# Papra_v0_10.net
KiCad netlist of a schematic drawn in EAGLE
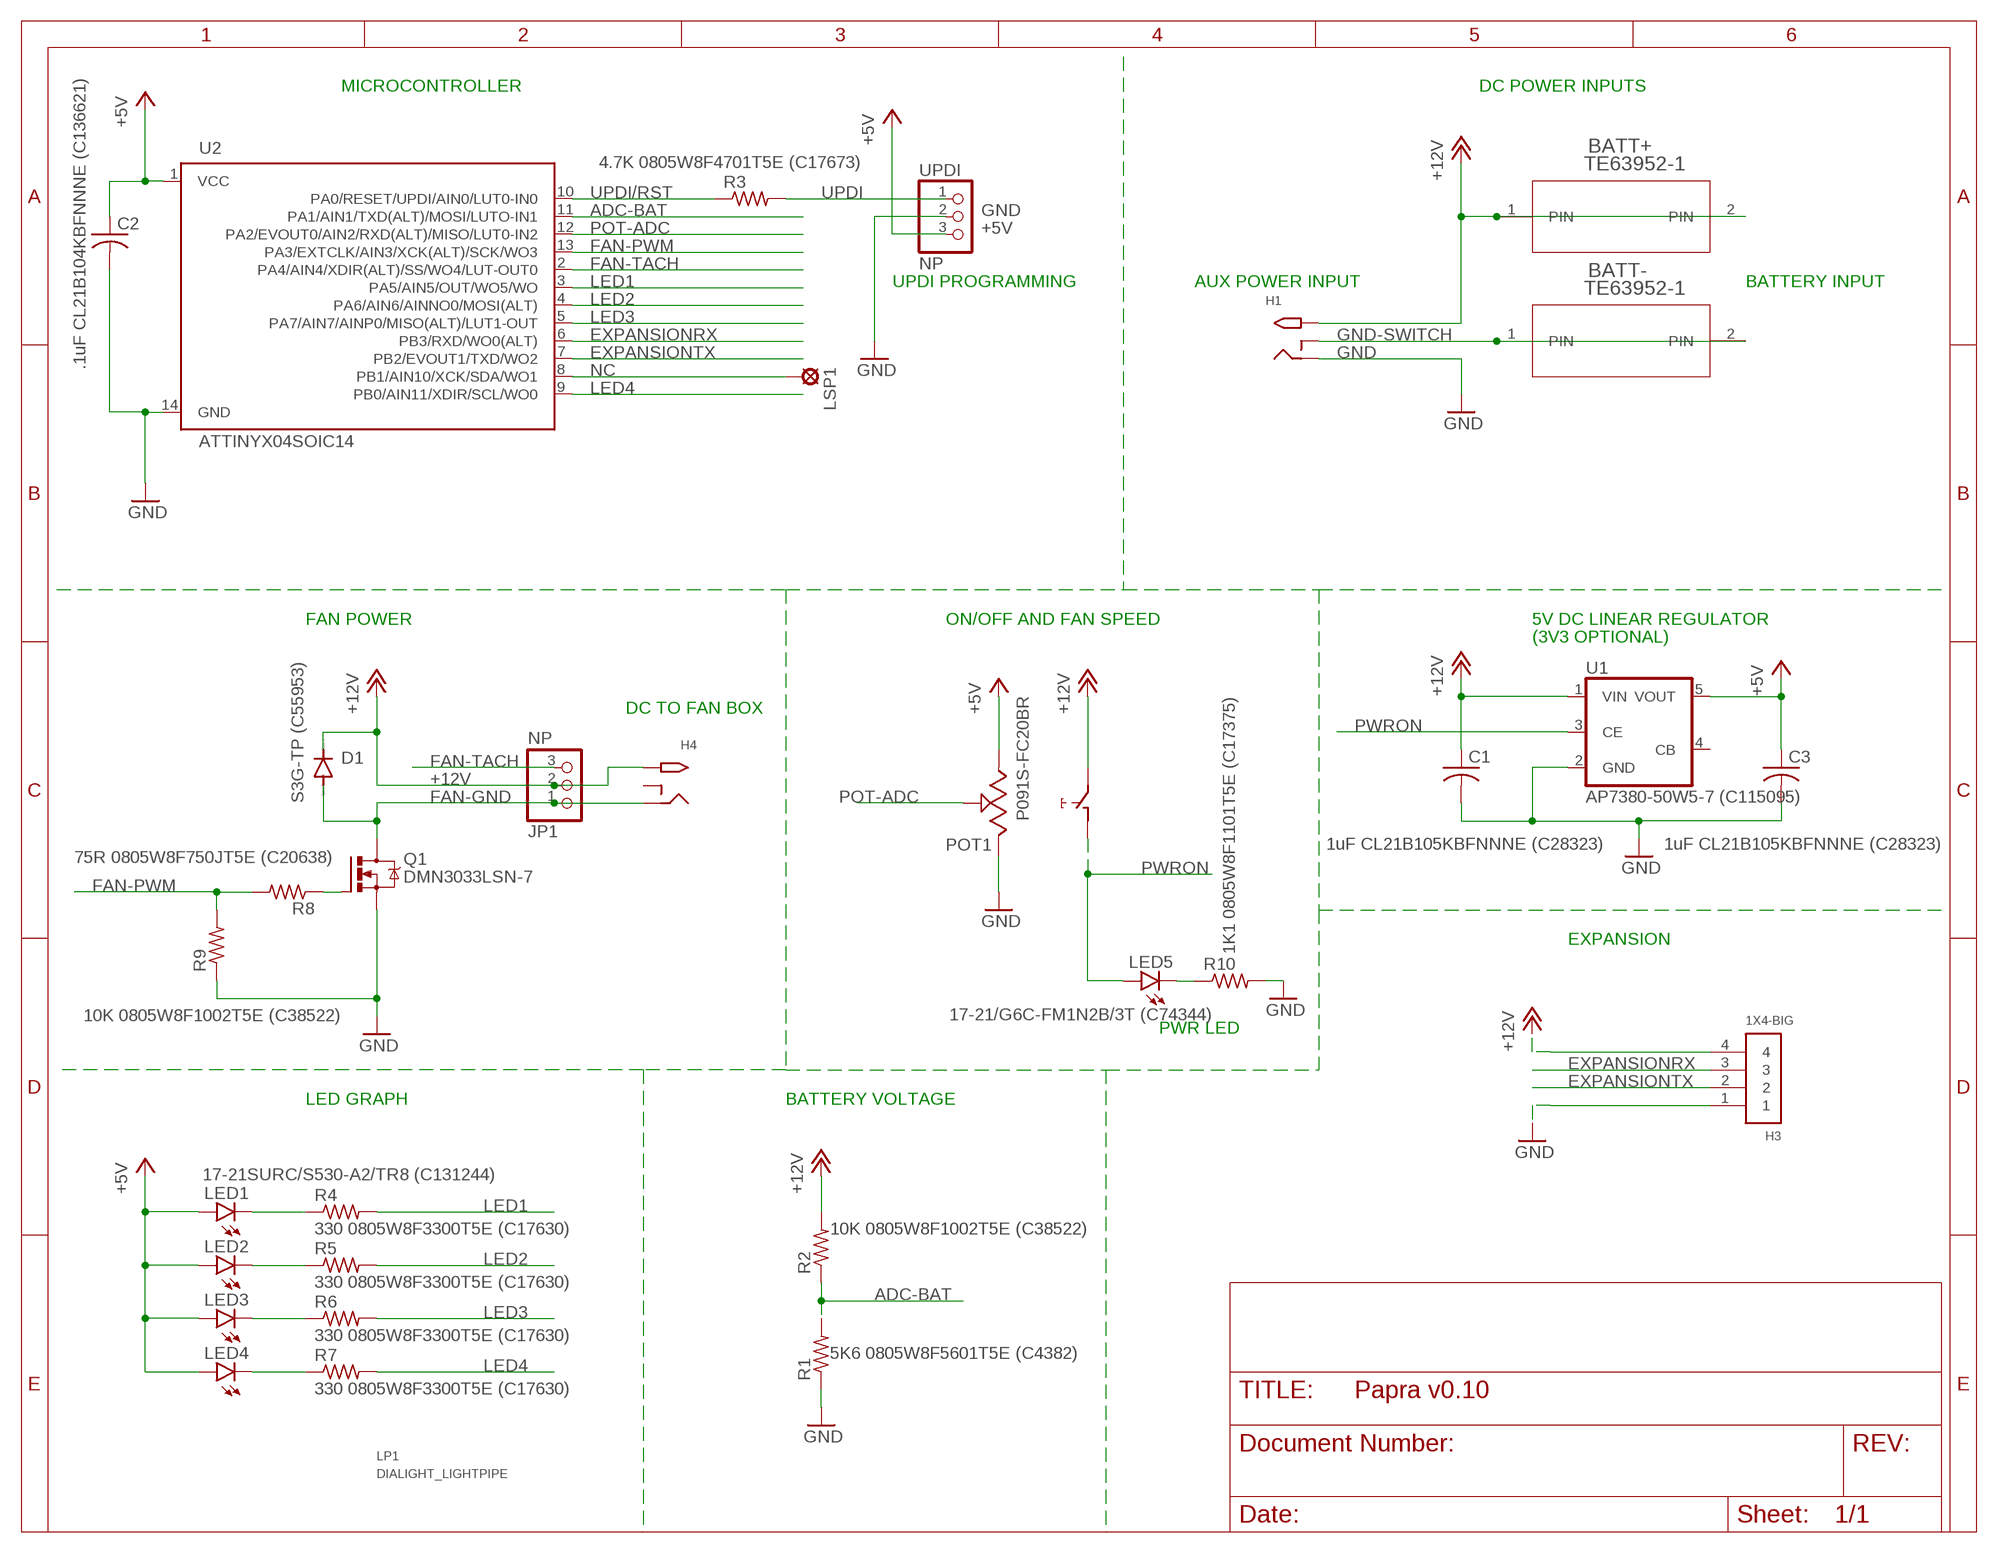
[diagram p0: schematic, sheet 1]

(export (version "E")
  (design (tool "Eeschema 10.0.6"))
  (components
    (comp (ref "BATT+")
      (value "TE63952-1")
      (footprint "eagle-import:TE63952-1")
      (libsource (lib "eagle-import") (part "TE63952-1"))
    )
    (comp (ref "BATT-")
      (value "TE63952-1")
      (footprint "eagle-import:TE63952-1")
      (libsource (lib "eagle-import") (part "TE63952-1"))
    )
    (comp (ref "C1")
      (value "1uF CL21B105KBFNNNE (C28323)")
      (footprint "eagle-import:C0805")
      (libsource (lib "eagle-import") (part "C-USC0805"))
    )
    (comp (ref "C2")
      (value ".1uF CL21B104KBFNNNE (C136621)")
      (footprint "eagle-import:C0805")
      (libsource (lib "eagle-import") (part "C-USC0805"))
    )
    (comp (ref "C3")
      (value "1uF CL21B105KBFNNNE (C28323)")
      (footprint "eagle-import:C0805")
      (libsource (lib "eagle-import") (part "C-USC0805"))
    )
    (comp (ref "D1")
      (value "S3G-TP (C55953)")
      (footprint "eagle-import:SMC")
      (libsource (lib "eagle-import") (part "DIODE-SMC"))
    )
    (comp (ref "H1")
      (value "M-CUI-PJ-066A")
      (footprint "eagle-import:DCJACK-PJ-066A")
      (libsource (lib "eagle-import") (part "PJ-066A"))
    )
    (comp (ref "H3")
      (value "1X4-BIG")
      (footprint "eagle-import:1X04-BIG")
      (libsource (lib "eagle-import") (part "1X4-BIG"))
    )
    (comp (ref "H4")
      (value "M-CUI-PJ-066A")
      (footprint "eagle-import:DCJACK-PJ-066A")
      (libsource (lib "eagle-import") (part "PJ-066A"))
    )
    (comp (ref "JP1")
      (value "NP")
      (footprint "eagle-import:1X03")
      (libsource (lib "eagle-import") (part "PINHD-1X3"))
    )
    (comp (ref "LED1")
      (value "17-21SURC/S530-A2/TR8 (C131244)")
      (footprint "eagle-import:CHIPLED_0805")
      (libsource (lib "eagle-import") (part "LEDCHIPLED_0805"))
    )
    (comp (ref "LED2")
      (value "17-21SURC/S530-A2/TR8 (C131244)")
      (footprint "eagle-import:CHIPLED_0805")
      (libsource (lib "eagle-import") (part "LEDCHIPLED_0805"))
    )
    (comp (ref "LED3")
      (value "17-21SURC/S530-A2/TR8 (C131244)")
      (footprint "eagle-import:CHIPLED_0805")
      (libsource (lib "eagle-import") (part "LEDCHIPLED_0805"))
    )
    (comp (ref "LED4")
      (value "17-21SURC/S530-A2/TR8 (C131244)")
      (footprint "eagle-import:CHIPLED_0805")
      (libsource (lib "eagle-import") (part "LEDCHIPLED_0805"))
    )
    (comp (ref "LED5")
      (value "17-21/G6C-FM1N2B/3T (C74344)")
      (footprint "eagle-import:CHIPLED_0805")
      (libsource (lib "eagle-import") (part "LEDCHIPLED_0805"))
    )
    (comp (ref "LP1")
      (value "DIALIGHT_LIGHTPIPE")
      (footprint "eagle-import:DIALIGHT_5151020F__LEDS")
      (libsource (lib "eagle-import") (part "DIALIGHT_LIGHTPIPE"))
    )
    (comp (ref "LSP1")
      (value "SE13")
      (footprint "eagle-import:SE13")
      (libsource (lib "eagle-import") (part "SE13"))
    )
    (comp (ref "POT1")
      (value "P091S-FC20BR")
      (footprint "eagle-import:P091S-FC20BR")
      (libsource (lib "eagle-import") (part "P091S-FC20BR"))
    )
    (comp (ref "Q1")
      (value "DMN3033LSN-7")
      (footprint "eagle-import:SOT23")
      (libsource (lib "eagle-import") (part "NMOSFETSOT23"))
    )
    (comp (ref "R1")
      (value "5K6 0805W8F5601T5E (C4382)")
      (footprint "eagle-import:R0805")
      (libsource (lib "eagle-import") (part "R-US_R0805"))
    )
    (comp (ref "R2")
      (value "10K 0805W8F1002T5E (C38522)")
      (footprint "eagle-import:R0805")
      (libsource (lib "eagle-import") (part "R-US_R0805"))
    )
    (comp (ref "R3")
      (value "4.7K 0805W8F4701T5E (C17673)")
      (footprint "eagle-import:R0805")
      (libsource (lib "eagle-import") (part "R-US_R0805"))
    )
    (comp (ref "R4")
      (value "330 0805W8F3300T5E (C17630)")
      (footprint "eagle-import:R0805")
      (libsource (lib "eagle-import") (part "R-US_R0805"))
    )
    (comp (ref "R5")
      (value "330 0805W8F3300T5E (C17630)")
      (footprint "eagle-import:R0805")
      (libsource (lib "eagle-import") (part "R-US_R0805"))
    )
    (comp (ref "R6")
      (value "330 0805W8F3300T5E (C17630)")
      (footprint "eagle-import:R0805")
      (libsource (lib "eagle-import") (part "R-US_R0805"))
    )
    (comp (ref "R7")
      (value "330 0805W8F3300T5E (C17630)")
      (footprint "eagle-import:R0805")
      (libsource (lib "eagle-import") (part "R-US_R0805"))
    )
    (comp (ref "R8")
      (value "75R 0805W8F750JT5E (C20638)")
      (footprint "eagle-import:R0805")
      (libsource (lib "eagle-import") (part "R-US_R0805"))
    )
    (comp (ref "R9")
      (value "10K 0805W8F1002T5E (C38522)")
      (footprint "eagle-import:R0805")
      (libsource (lib "eagle-import") (part "R-US_R0805"))
    )
    (comp (ref "R10")
      (value "1K1 0805W8F1101T5E (C17375)")
      (footprint "eagle-import:R0805")
      (libsource (lib "eagle-import") (part "R-US_R0805"))
    )
    (comp (ref "U1")
      (value "AP7380-50W5-7 (C115095)")
      (footprint "eagle-import:SOT25")
      (libsource (lib "eagle-import") (part "TS520533"))
    )
    (comp (ref "U2")
      (value "ATTINYX04SOIC14")
      (footprint "eagle-import:SOIC127P600X144-14")
      (libsource (lib "eagle-import") (part "ATTINYX04SOIC14"))
    )
    (comp (ref "UPDI")
      (value "NP")
      (footprint "eagle-import:1X03")
      (libsource (lib "eagle-import") (part "PINHD-1X3"))
    )
  )
  (nets
    (net (code "1") (name "+5V") (class "Default")
      (node (ref "C2") (pin "1") (pinfunction "1_1") (pintype "passive"))
      (node (ref "C3") (pin "1") (pinfunction "1_1") (pintype "passive"))
      (node (ref "LED1") (pin "A") (pinfunction "A_A") (pintype "passive"))
      (node (ref "LED2") (pin "A") (pinfunction "A_A") (pintype "passive"))
      (node (ref "LED3") (pin "A") (pinfunction "A_A") (pintype "passive"))
      (node (ref "LED4") (pin "A") (pinfunction "A_A") (pintype "passive"))
      (node (ref "POT1") (pin "1") (pinfunction "1_1") (pintype "passive"))
      (node (ref "U1") (pin "5") (pinfunction "VOUT_5") (pintype "passive"))
      (node (ref "U2") (pin "1") (pinfunction "VCC_1") (pintype "power_in"))
      (node (ref "UPDI") (pin "3") (pinfunction "3_3") (pintype "passive"))
    )
    (net (code "2") (name "+12V") (class "Default")
      (node (ref "BATT+") (pin "1") (pinfunction "PIN_1") (pintype "passive"))
      (node (ref "BATT+") (pin "2") (pinfunction "PIN_2") (pintype "passive"))
      (node (ref "C1") (pin "1") (pinfunction "1_1") (pintype "passive"))
      (node (ref "D1") (pin "C") (pinfunction "C_C") (pintype "passive"))
      (node (ref "H1") (pin "PWR") (pinfunction "TIP_PWR") (pintype "bidirectional"))
      (node (ref "H3") (pin "4") (pinfunction "4_4") (pintype "bidirectional"))
      (node (ref "H4") (pin "PWR") (pinfunction "TIP_PWR") (pintype "bidirectional"))
      (node (ref "JP1") (pin "2") (pinfunction "2_2") (pintype "passive"))
      (node (ref "POT1") (pin "NO") (pinfunction "5_NO") (pintype "passive"))
      (node (ref "R2") (pin "2") (pinfunction "2_2") (pintype "passive"))
      (node (ref "U1") (pin "1") (pinfunction "VIN_1") (pintype "input"))
    )
    (net (code "3") (name "/ADC-BAT") (class "Default")
      (node (ref "R1") (pin "2") (pinfunction "2_2") (pintype "passive"))
      (node (ref "R2") (pin "1") (pinfunction "1_1") (pintype "passive"))
      (node (ref "U2") (pin "11") (pinfunction "PA1/AIN1/TXD(ALT)/MOSI/LUTO-IN1_11") (pintype "bidirectional"))
    )
    (net (code "4") (name "/EXPANSIONRX") (class "Default")
      (node (ref "H3") (pin "3") (pinfunction "3_3") (pintype "bidirectional"))
      (node (ref "U2") (pin "6") (pinfunction "PB3/RXD/WO0(ALT)_6") (pintype "bidirectional"))
    )
    (net (code "5") (name "/EXPANSIONTX") (class "Default")
      (node (ref "H3") (pin "2") (pinfunction "2_2") (pintype "bidirectional"))
      (node (ref "U2") (pin "7") (pinfunction "PB2/EVOUT1/TXD/WO2_7") (pintype "bidirectional"))
    )
    (net (code "6") (name "/FAN-GND") (class "Default")
      (node (ref "D1") (pin "A") (pinfunction "A_A") (pintype "passive"))
      (node (ref "H4") (pin "GND") (pinfunction "RING_GND") (pintype "bidirectional"))
      (node (ref "JP1") (pin "1") (pinfunction "1_1") (pintype "passive"))
      (node (ref "Q1") (pin "3") (pinfunction "D_3") (pintype "passive"))
    )
    (net (code "7") (name "/FAN-PWM") (class "Default")
      (node (ref "R8") (pin "2") (pinfunction "2_2") (pintype "passive"))
      (node (ref "R9") (pin "2") (pinfunction "2_2") (pintype "passive"))
      (node (ref "U2") (pin "13") (pinfunction "PA3/EXTCLK/AIN3/XCK(ALT)/SCK/WO3_13") (pintype "bidirectional"))
    )
    (net (code "8") (name "/FAN-TACH") (class "Default")
      (node (ref "JP1") (pin "3") (pinfunction "3_3") (pintype "passive"))
      (node (ref "U2") (pin "2") (pinfunction "PA4/AIN4/XDIR(ALT)/SS/WO4/LUT-OUT0_2") (pintype "bidirectional"))
    )
    (net (code "9") (name "/GND-SWITCH") (class "Default")
      (node (ref "BATT-") (pin "1") (pinfunction "PIN_1") (pintype "passive"))
      (node (ref "BATT-") (pin "2") (pinfunction "PIN_2") (pintype "passive"))
      (node (ref "H1") (pin "GNDBREAK") (pinfunction "RING_SW_GNDBREAK") (pintype "bidirectional"))
    )
    (net (code "10") (name "/LED1") (class "Default")
      (node (ref "R4") (pin "2") (pinfunction "2_2") (pintype "passive"))
      (node (ref "U2") (pin "3") (pinfunction "PA5/AIN5/OUT/WO5/WO_3") (pintype "bidirectional"))
    )
    (net (code "11") (name "/LED2") (class "Default")
      (node (ref "R5") (pin "2") (pinfunction "2_2") (pintype "passive"))
      (node (ref "U2") (pin "4") (pinfunction "PA6/AIN6/AINNO0/MOSI(ALT)_4") (pintype "bidirectional"))
    )
    (net (code "12") (name "/LED3") (class "Default")
      (node (ref "R6") (pin "2") (pinfunction "2_2") (pintype "passive"))
      (node (ref "U2") (pin "5") (pinfunction "PA7/AIN7/AINP0/MISO(ALT)/LUT1-OUT_5") (pintype "bidirectional"))
    )
    (net (code "13") (name "/LED4") (class "Default")
      (node (ref "R7") (pin "2") (pinfunction "2_2") (pintype "passive"))
      (node (ref "U2") (pin "9") (pinfunction "PB0/AIN11/XDIR/SCL/WO0_9") (pintype "bidirectional"))
    )
    (net (code "14") (name "/NC") (class "Default")
      (node (ref "LSP1") (pin "MP") (pinfunction "MP_MP") (pintype "passive"))
      (node (ref "U2") (pin "8") (pinfunction "PB1/AIN10/XCK/SDA/WO1_8") (pintype "bidirectional"))
    )
    (net (code "15") (name "/POT-ADC") (class "Default")
      (node (ref "POT1") (pin "2") (pinfunction "2_2") (pintype "passive"))
      (node (ref "U2") (pin "12") (pinfunction "PA2/EVOUT0/AIN2/RXD(ALT)/MISO/LUT0-IN2_12") (pintype "bidirectional"))
    )
    (net (code "16") (name "/PWRON") (class "Default")
      (node (ref "LED5") (pin "A") (pinfunction "A_A") (pintype "passive"))
      (node (ref "POT1") (pin "COM") (pinfunction "4_COM") (pintype "passive"))
      (node (ref "U1") (pin "3") (pinfunction "CE_3") (pintype "input"))
    )
    (net (code "17") (name "/UPDI") (class "Default")
      (node (ref "R3") (pin "2") (pinfunction "2_2") (pintype "passive"))
      (node (ref "UPDI") (pin "1") (pinfunction "1_1") (pintype "passive"))
    )
    (net (code "18") (name "/UPDI{slash}RST") (class "Default")
      (node (ref "R3") (pin "1") (pinfunction "1_1") (pintype "passive"))
      (node (ref "U2") (pin "10") (pinfunction "PA0/RESET/UPDI/AIN0/LUT0-IN0_10") (pintype "bidirectional"))
    )
    (net (code "19") (name "GND") (class "Default")
      (node (ref "C1") (pin "2") (pinfunction "2_2") (pintype "passive"))
      (node (ref "C2") (pin "2") (pinfunction "2_2") (pintype "passive"))
      (node (ref "C3") (pin "2") (pinfunction "2_2") (pintype "passive"))
      (node (ref "H1") (pin "GND") (pinfunction "RING_GND") (pintype "bidirectional"))
      (node (ref "H3") (pin "1") (pinfunction "1_1") (pintype "bidirectional"))
      (node (ref "POT1") (pin "3") (pinfunction "3_3") (pintype "passive"))
      (node (ref "Q1") (pin "2") (pinfunction "S_2") (pintype "passive"))
      (node (ref "R1") (pin "1") (pinfunction "1_1") (pintype "passive"))
      (node (ref "R10") (pin "2") (pinfunction "2_2") (pintype "passive"))
      (node (ref "R9") (pin "1") (pinfunction "1_1") (pintype "passive"))
      (node (ref "U1") (pin "2") (pinfunction "GND_2") (pintype "passive"))
      (node (ref "U2") (pin "14") (pinfunction "GND_14") (pintype "power_in"))
      (node (ref "UPDI") (pin "2") (pinfunction "2_2") (pintype "passive"))
    )
    (net (code "20") (name "Net-(LED1-PadC)") (class "Default")
      (node (ref "LED1") (pin "C") (pinfunction "C_C") (pintype "passive"))
      (node (ref "R4") (pin "1") (pinfunction "1_1") (pintype "passive"))
    )
    (net (code "21") (name "Net-(LED2-PadC)") (class "Default")
      (node (ref "LED2") (pin "C") (pinfunction "C_C") (pintype "passive"))
      (node (ref "R5") (pin "1") (pinfunction "1_1") (pintype "passive"))
    )
    (net (code "22") (name "Net-(LED3-PadC)") (class "Default")
      (node (ref "LED3") (pin "C") (pinfunction "C_C") (pintype "passive"))
      (node (ref "R6") (pin "1") (pinfunction "1_1") (pintype "passive"))
    )
    (net (code "23") (name "Net-(LED4-PadC)") (class "Default")
      (node (ref "LED4") (pin "C") (pinfunction "C_C") (pintype "passive"))
      (node (ref "R7") (pin "1") (pinfunction "1_1") (pintype "passive"))
    )
    (net (code "24") (name "Net-(LED5-PadC)") (class "Default")
      (node (ref "LED5") (pin "C") (pinfunction "C_C") (pintype "passive"))
      (node (ref "R10") (pin "1") (pinfunction "1_1") (pintype "passive"))
    )
    (net (code "25") (name "Net-(Q1-G)") (class "Default")
      (node (ref "Q1") (pin "1") (pinfunction "G_1") (pintype "passive"))
      (node (ref "R8") (pin "1") (pinfunction "1_1") (pintype "passive"))
    )
    (net (code "26") (name "unconnected-(H4-RING_SW-PadGNDBREAK)") (class "Default")
      (node (ref "H4") (pin "GNDBREAK") (pinfunction "RING_SW_GNDBREAK") (pintype "bidirectional"))
    )
    (net (code "27") (name "unconnected-(U1-CB-Pad4)") (class "Default")
      (node (ref "U1") (pin "4") (pinfunction "CB_4") (pintype "input"))
    )
  )
)
